# EE445L_Baseline_Schematic.net
KiCad netlist of a schematic drawn in EAGLE
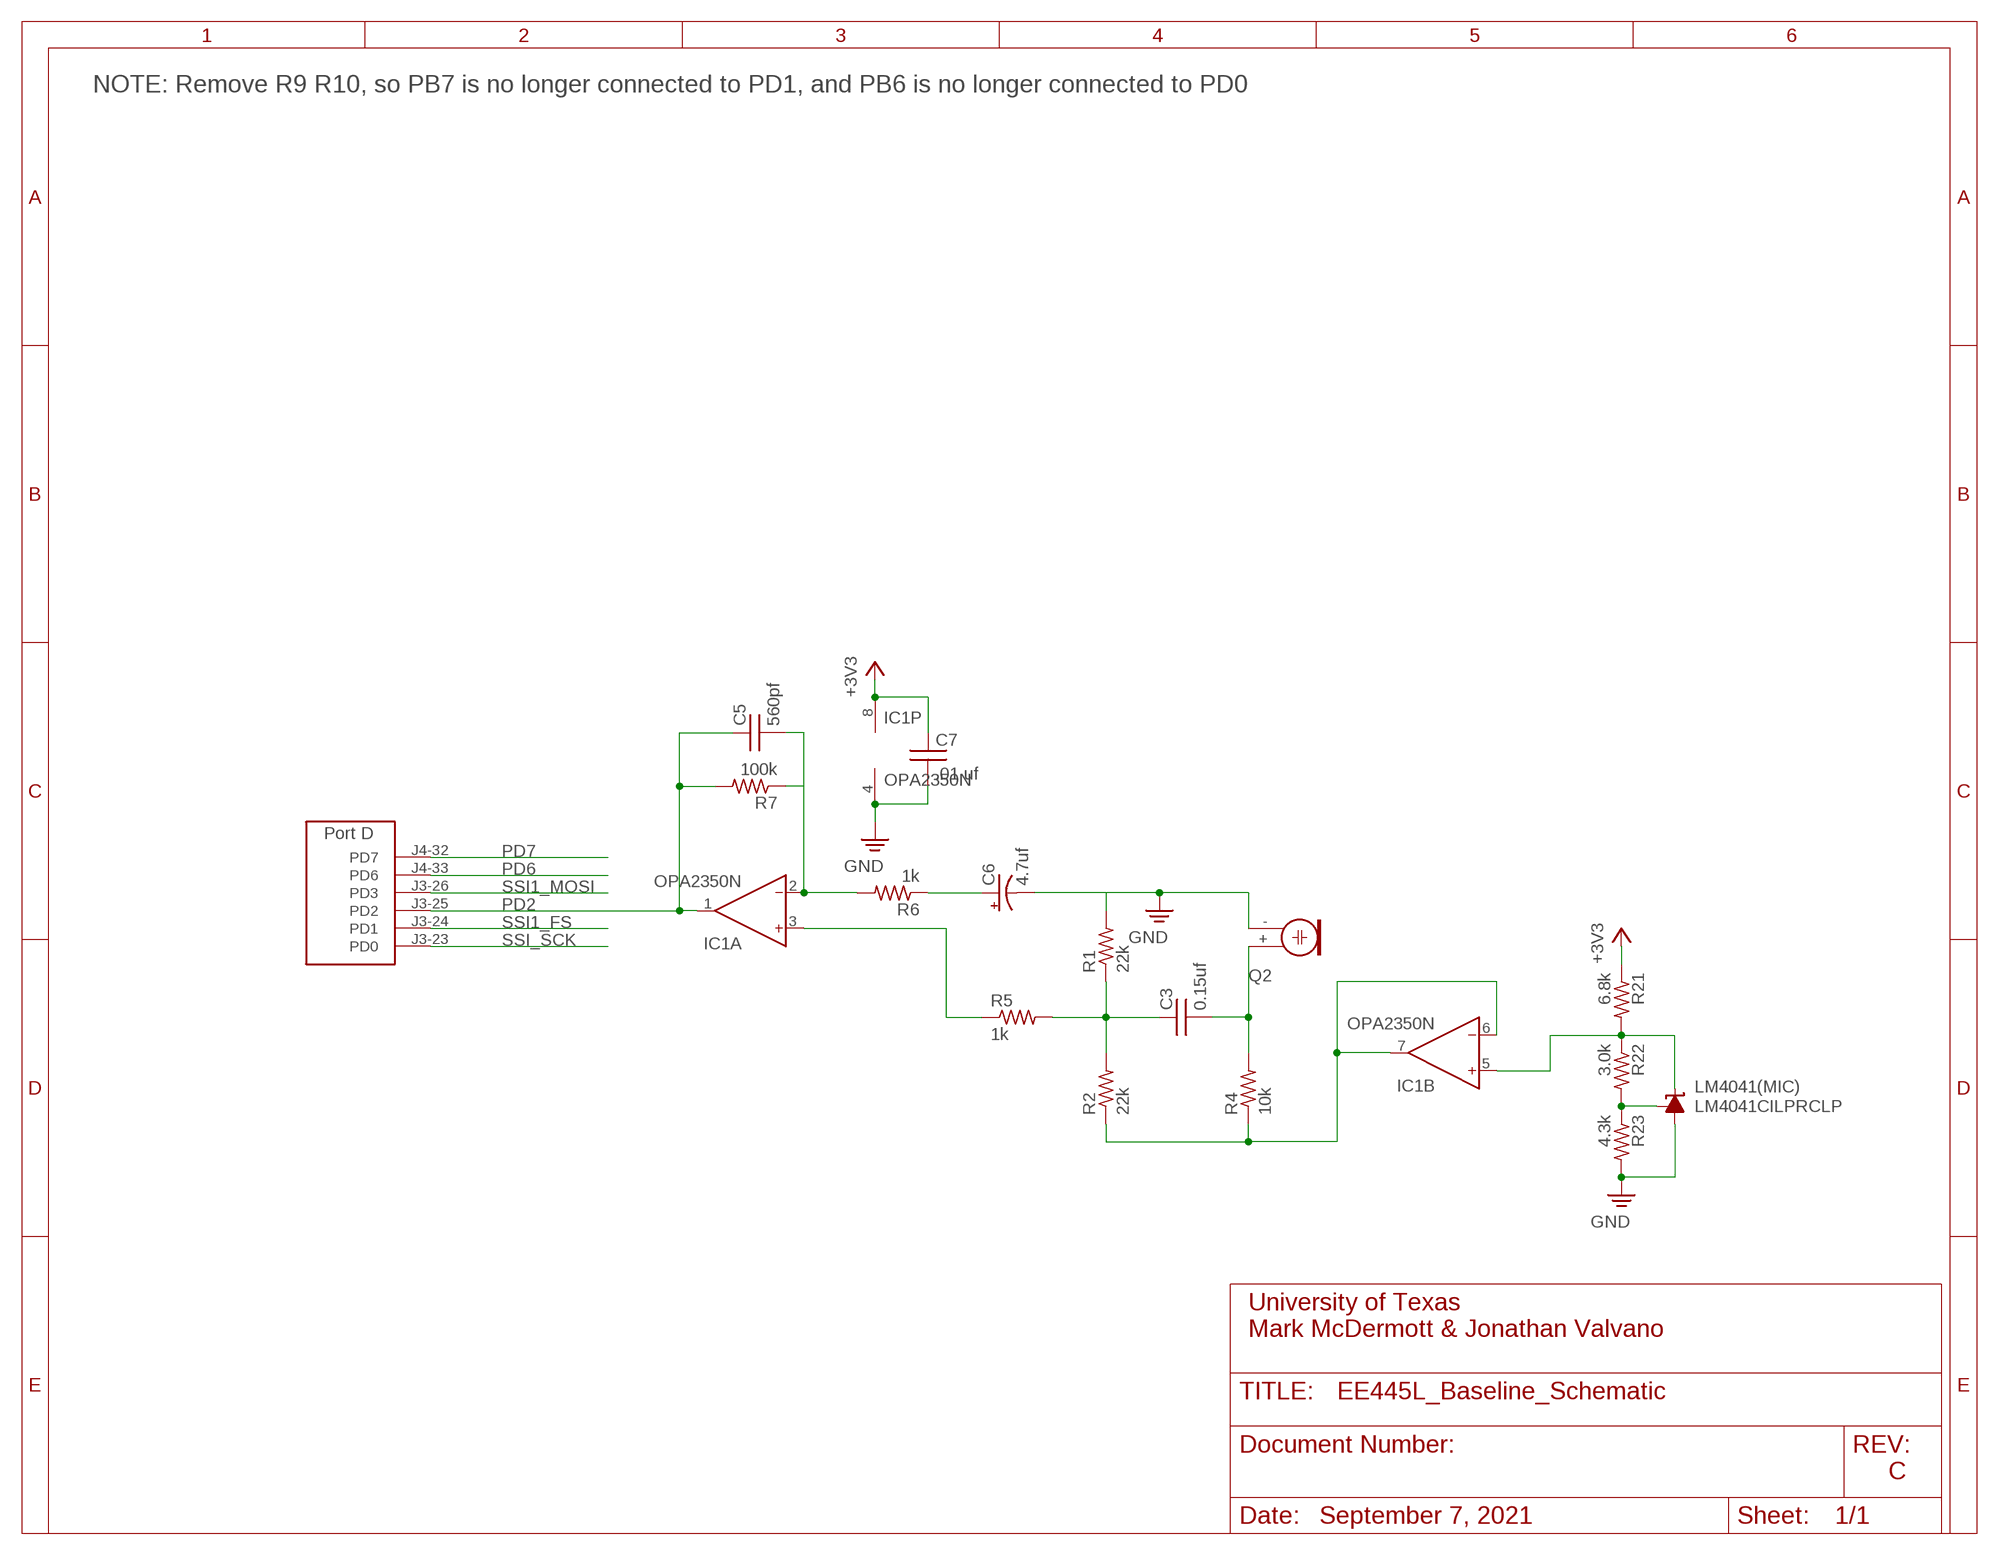
[diagram p0: schematic, sheet 1, part 1 of 2]
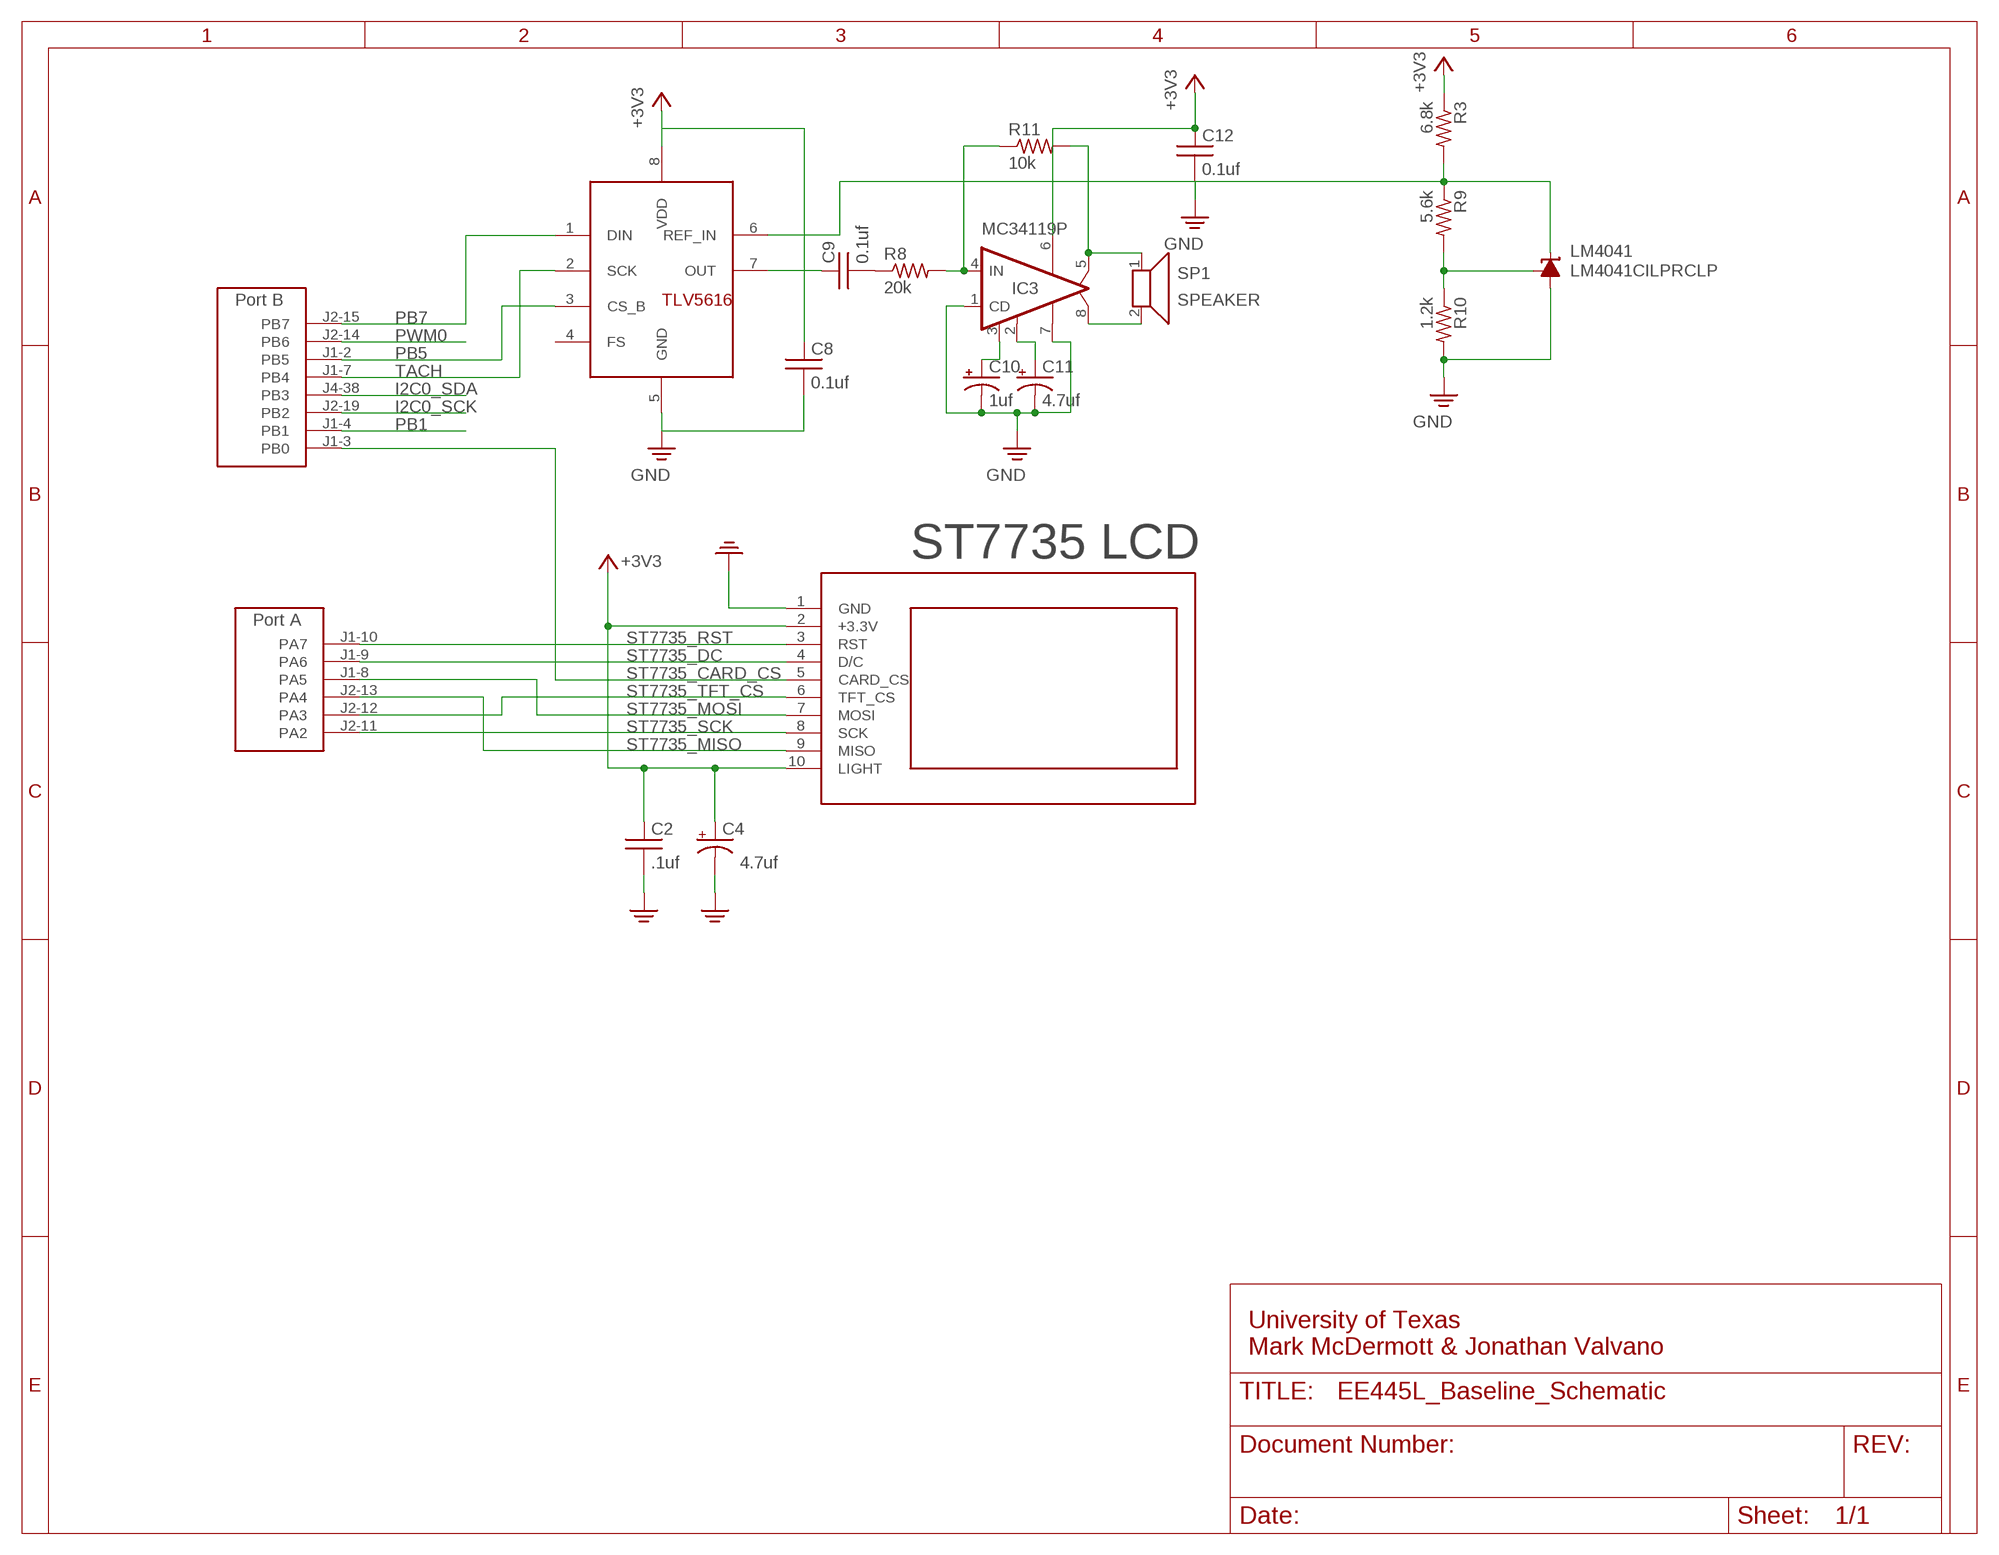
[diagram p1: schematic, sheet 1, part 2 of 2]

(export (version "E")
  (design (tool "Eeschema 10.0.6"))
  (components
    (comp (ref "C2")
      (value ".1uf")
      (footprint "eagle-import:CAP200MIL")
      (libsource (lib "eagle-import") (part "CAPACITOR050-024X044"))
    )
    (comp (ref "C3")
      (value "0.15uf")
      (footprint "eagle-import:CAP100MIL")
      (libsource (lib "eagle-import") (part "CAPACITOR025-024X044"))
    )
    (comp (ref "C4")
      (value "4.7uf")
      (footprint "eagle-import:CAP200MILPOLARIZED")
      (libsource (lib "eagle-import") (part "CAPACITOR_POLARIZEDE5-6"))
    )
    (comp (ref "C5")
      (value "560pf")
      (footprint "eagle-import:CAP100MIL")
      (libsource (lib "eagle-import") (part "CAPACITOR025-024X044"))
    )
    (comp (ref "C6")
      (value "4.7uf")
      (footprint "eagle-import:CAP200MILPOLARIZED")
      (libsource (lib "eagle-import") (part "CAPACITOR_POLARIZEDE5-6"))
    )
    (comp (ref "C7")
      (value ".01 uf")
      (footprint "eagle-import:CAP100MIL")
      (libsource (lib "eagle-import") (part "CAPACITOR025-024X044"))
    )
    (comp (ref "C8")
      (value "0.1uf")
      (footprint "eagle-import:CAP100MIL")
      (libsource (lib "eagle-import") (part "CAPACITOR025-024X044"))
    )
    (comp (ref "C9")
      (value "0.1uf")
      (footprint "eagle-import:CAP100MIL")
      (libsource (lib "eagle-import") (part "CAPACITOR025-024X044"))
    )
    (comp (ref "C10")
      (value "1uf")
      (footprint "eagle-import:CAP200MILPOLARIZED")
      (libsource (lib "eagle-import") (part "CAPACITOR_POLARIZEDE5-6"))
    )
    (comp (ref "C11")
      (value "4.7uf")
      (footprint "eagle-import:CAP200MILPOLARIZED")
      (libsource (lib "eagle-import") (part "CAPACITOR_POLARIZEDE5-6"))
    )
    (comp (ref "C12")
      (value "0.1uf")
      (footprint "eagle-import:CAP100MIL")
      (libsource (lib "eagle-import") (part "CAPACITOR025-024X044"))
    )
    (comp (ref "IC1")
      (value "OPA2350N")
      (footprint "eagle-import:DIL08")
      (libsource (lib "eagle-import") (part "OPA2350N"))
    )
    (comp (ref "IC3")
      (value "MC34119P")
      (footprint "eagle-import:DIL08")
      (libsource (lib "eagle-import") (part "MC34119P"))
    )
    (comp (ref "LM4041")
      (value "LM4041CILPRCLP")
      (footprint "eagle-import:LP_O-PBCY-W3")
      (fields (field (name "MPN") "LM4041CILP"))
      (libsource (lib "eagle-import") (part "LM4041CILPRLPC"))
    )
    (comp (ref "LM4041(MIC)")
      (value "LM4041CILPRCLP")
      (footprint "eagle-import:LP_O-PBCY-W3")
      (fields (field (name "MPN") "LM4041CILP"))
      (libsource (lib "eagle-import") (part "LM4041CILPRLPC"))
    )
    (comp (ref "Q2")
      (value "ELECTRET")
      (footprint "eagle-import:9.7ELECTRET")
      (libsource (lib "eagle-import") (part "ELECTRET"))
    )
    (comp (ref "R1")
      (value "22k")
      (footprint "eagle-import:RES200MIL")
      (libsource (lib "eagle-import") (part "RESISTOR0204/5"))
    )
    (comp (ref "R2")
      (value "22k")
      (footprint "eagle-import:RES200MIL")
      (libsource (lib "eagle-import") (part "RESISTOR0204/5"))
    )
    (comp (ref "R3")
      (value "6.8k")
      (footprint "eagle-import:RES300MIL")
      (libsource (lib "eagle-import") (part "RESISTOR0204/7"))
    )
    (comp (ref "R4")
      (value "10k")
      (footprint "eagle-import:RES200MIL")
      (libsource (lib "eagle-import") (part "RESISTOR0204/5"))
    )
    (comp (ref "R5")
      (value "1k")
      (footprint "eagle-import:RES200MIL")
      (libsource (lib "eagle-import") (part "RESISTOR0204/5"))
    )
    (comp (ref "R6")
      (value "1k")
      (footprint "eagle-import:RES200MIL")
      (libsource (lib "eagle-import") (part "RESISTOR0204/5"))
    )
    (comp (ref "R7")
      (value "100k")
      (footprint "eagle-import:RES200MIL")
      (libsource (lib "eagle-import") (part "RESISTOR0204/5"))
    )
    (comp (ref "R8")
      (value "20k")
      (footprint "eagle-import:RES200MIL")
      (libsource (lib "eagle-import") (part "RESISTOR0204/5"))
    )
    (comp (ref "R9")
      (value "5.6k")
      (footprint "eagle-import:RES300MIL")
      (libsource (lib "eagle-import") (part "RESISTOR0204/7"))
    )
    (comp (ref "R10")
      (value "1.2k")
      (footprint "eagle-import:RES300MIL")
      (libsource (lib "eagle-import") (part "RESISTOR0204/7"))
    )
    (comp (ref "R11")
      (value "10k")
      (footprint "eagle-import:RES300MIL")
      (libsource (lib "eagle-import") (part "RESISTOR0204/7"))
    )
    (comp (ref "R21")
      (value "6.8k")
      (footprint "eagle-import:RES300MIL")
      (libsource (lib "eagle-import") (part "RESISTOR0204/7"))
    )
    (comp (ref "R22")
      (value "3.0k")
      (footprint "eagle-import:RES300MIL")
      (libsource (lib "eagle-import") (part "RESISTOR0204/7"))
    )
    (comp (ref "R23")
      (value "4.3k")
      (footprint "eagle-import:RES300MIL")
      (libsource (lib "eagle-import") (part "RESISTOR0204/7"))
    )
    (comp (ref "SP1")
      (value "SPEAKER")
      (footprint "eagle-import:1X02")
      (libsource (lib "eagle-import") (part "SPEAKER"))
    )
    (comp (ref "U$1")
      (value "TLV5616")
      (footprint "eagle-import:DIL08")
      (libsource (lib "eagle-import") (part "TLV5616"))
    )
    (comp (ref "U$2")
      (value "TM4C_BP")
      (footprint "eagle-import:TM4C_BOOSTER_PACK")
      (libsource (lib "eagle-import") (part "TM4C_BP"))
    )
    (comp (ref "U$3")
      (value "ST7735")
      (footprint "eagle-import:ST7735")
      (libsource (lib "eagle-import") (part "ST7735"))
    )
  )
  (nets
    (net (code "1") (name "+3V3") (class "Default")
      (node (ref "C12") (pin "1") (pinfunction "1_1") (pintype "passive"))
      (node (ref "C2") (pin "1") (pinfunction "1_1") (pintype "passive"))
      (node (ref "C4") (pin "+") (pinfunction "+_+") (pintype "passive"))
      (node (ref "C7") (pin "1") (pinfunction "1_1") (pintype "passive"))
      (node (ref "C8") (pin "1") (pinfunction "1_1") (pintype "passive"))
      (node (ref "IC1") (pin "8") (pinfunction "V+_8") (pintype "power_in"))
      (node (ref "IC3") (pin "6") (pinfunction "VCC_6") (pintype "power_in"))
      (node (ref "R21") (pin "1") (pinfunction "1_1") (pintype "passive"))
      (node (ref "R3") (pin "1") (pinfunction "1_1") (pintype "passive"))
      (node (ref "U$1") (pin "8") (pinfunction "VDD_8") (pintype "bidirectional"))
      (node (ref "U$3") (pin "10") (pinfunction "LIGHT_10") (pintype "bidirectional"))
      (node (ref "U$3") (pin "2") (pinfunction "+3.3V_2") (pintype "bidirectional"))
    )
    (net (code "2") (name "/I2C0_SCK") (class "Default")
      (node (ref "U$2") (pin "J2-19") (pinfunction "PB2_J2-19") (pintype "bidirectional"))
    )
    (net (code "3") (name "/I2C0_SDA") (class "Default")
      (node (ref "U$2") (pin "J4-38") (pinfunction "PB3_J4-38") (pintype "bidirectional"))
    )
    (net (code "4") (name "/PB1") (class "Default")
      (node (ref "U$2") (pin "J1-4") (pinfunction "PB1_J1-4") (pintype "bidirectional"))
    )
    (net (code "5") (name "/PB5") (class "Default")
      (node (ref "U$1") (pin "3") (pinfunction "CS_B_3") (pintype "bidirectional"))
      (node (ref "U$2") (pin "J1-2") (pinfunction "PB5_J1-2") (pintype "bidirectional"))
    )
    (net (code "6") (name "/PB7") (class "Default")
      (node (ref "U$1") (pin "1") (pinfunction "DIN_1") (pintype "bidirectional"))
      (node (ref "U$2") (pin "J2-15") (pinfunction "PB7_J2-15") (pintype "bidirectional"))
    )
    (net (code "7") (name "/PD2") (class "Default")
      (node (ref "C5") (pin "1") (pinfunction "1_1") (pintype "passive"))
      (node (ref "IC1") (pin "1") (pinfunction "OUT_1") (pintype "output"))
      (node (ref "R7") (pin "2") (pinfunction "2_2") (pintype "passive"))
      (node (ref "U$2") (pin "J3-25") (pinfunction "PD2_J3-25") (pintype "bidirectional"))
    )
    (net (code "8") (name "/PD6") (class "Default")
      (node (ref "U$2") (pin "J4-33") (pinfunction "PD6_J4-33") (pintype "bidirectional"))
    )
    (net (code "9") (name "/PD7") (class "Default")
      (node (ref "U$2") (pin "J4-32") (pinfunction "PD7_J4-32") (pintype "bidirectional"))
    )
    (net (code "10") (name "/PWM0") (class "Default")
      (node (ref "U$2") (pin "J2-14") (pinfunction "PB6_J2-14") (pintype "bidirectional"))
    )
    (net (code "11") (name "/SSI1_FS") (class "Default")
      (node (ref "U$2") (pin "J3-24") (pinfunction "PD1_J3-24") (pintype "bidirectional"))
    )
    (net (code "12") (name "/SSI1_MOSI") (class "Default")
      (node (ref "U$2") (pin "J3-26") (pinfunction "PD3_J3-26") (pintype "bidirectional"))
    )
    (net (code "13") (name "/SSI_SCK") (class "Default")
      (node (ref "U$2") (pin "J3-23") (pinfunction "PD0_J3-23") (pintype "bidirectional"))
    )
    (net (code "14") (name "/ST7735_CARD_CS") (class "Default")
      (node (ref "U$2") (pin "J1-3") (pinfunction "PB0_J1-3") (pintype "bidirectional"))
      (node (ref "U$3") (pin "5") (pinfunction "CARD_CS_5") (pintype "bidirectional"))
    )
    (net (code "15") (name "/ST7735_DC") (class "Default")
      (node (ref "U$2") (pin "J1-9") (pinfunction "PA6_J1-9") (pintype "bidirectional"))
      (node (ref "U$3") (pin "4") (pinfunction "D/C_4") (pintype "bidirectional"))
    )
    (net (code "16") (name "/ST7735_MISO") (class "Default")
      (node (ref "U$2") (pin "J2-13") (pinfunction "PA4_J2-13") (pintype "bidirectional"))
      (node (ref "U$3") (pin "9") (pinfunction "MISO_9") (pintype "bidirectional"))
    )
    (net (code "17") (name "/ST7735_MOSI") (class "Default")
      (node (ref "U$2") (pin "J1-8") (pinfunction "PA5_J1-8") (pintype "bidirectional"))
      (node (ref "U$3") (pin "7") (pinfunction "MOSI_7") (pintype "bidirectional"))
    )
    (net (code "18") (name "/ST7735_RST") (class "Default")
      (node (ref "U$2") (pin "J1-10") (pinfunction "PA7_J1-10") (pintype "bidirectional"))
      (node (ref "U$3") (pin "3") (pinfunction "RST_3") (pintype "bidirectional"))
    )
    (net (code "19") (name "/ST7735_SCK") (class "Default")
      (node (ref "U$2") (pin "J2-11") (pinfunction "PA2_J2-11") (pintype "bidirectional"))
      (node (ref "U$3") (pin "8") (pinfunction "SCK_8") (pintype "bidirectional"))
    )
    (net (code "20") (name "/ST7735_TFT_CS") (class "Default")
      (node (ref "U$2") (pin "J2-12") (pinfunction "PA3_J2-12") (pintype "bidirectional"))
      (node (ref "U$3") (pin "6") (pinfunction "TFT_CS_6") (pintype "bidirectional"))
    )
    (net (code "21") (name "/TACH") (class "Default")
      (node (ref "U$1") (pin "2") (pinfunction "SCK_2") (pintype "bidirectional"))
      (node (ref "U$2") (pin "J1-7") (pinfunction "PB4_J1-7") (pintype "bidirectional"))
    )
    (net (code "22") (name "GND") (class "Default")
      (node (ref "C10") (pin "-") (pinfunction "-_-") (pintype "passive"))
      (node (ref "C11") (pin "-") (pinfunction "-_-") (pintype "passive"))
      (node (ref "C12") (pin "2") (pinfunction "2_2") (pintype "passive"))
      (node (ref "C2") (pin "2") (pinfunction "2_2") (pintype "passive"))
      (node (ref "C4") (pin "-") (pinfunction "-_-") (pintype "passive"))
      (node (ref "C6") (pin "-") (pinfunction "-_-") (pintype "passive"))
      (node (ref "C7") (pin "2") (pinfunction "2_2") (pintype "passive"))
      (node (ref "C8") (pin "2") (pinfunction "2_2") (pintype "passive"))
      (node (ref "IC1") (pin "4") (pinfunction "V-_4") (pintype "power_in"))
      (node (ref "IC3") (pin "1") (pinfunction "CD_1") (pintype "passive"))
      (node (ref "IC3") (pin "7") (pinfunction "GND_7") (pintype "power_in"))
      (node (ref "LM4041") (pin "3") (pinfunction "A_3") (pintype "passive"))
      (node (ref "LM4041(MIC)") (pin "3") (pinfunction "A_3") (pintype "passive"))
      (node (ref "Q2") (pin "-") (pinfunction "1_-") (pintype "passive"))
      (node (ref "R1") (pin "2") (pinfunction "2_2") (pintype "passive"))
      (node (ref "R10") (pin "2") (pinfunction "2_2") (pintype "passive"))
      (node (ref "R23") (pin "2") (pinfunction "2_2") (pintype "passive"))
      (node (ref "U$1") (pin "5") (pinfunction "GND_5") (pintype "bidirectional"))
      (node (ref "U$3") (pin "1") (pinfunction "GND_1") (pintype "bidirectional"))
    )
    (net (code "23") (name "Net-(C3-Pad1)") (class "Default")
      (node (ref "C3") (pin "1") (pinfunction "1_1") (pintype "passive"))
      (node (ref "R1") (pin "1") (pinfunction "1_1") (pintype "passive"))
      (node (ref "R2") (pin "2") (pinfunction "2_2") (pintype "passive"))
      (node (ref "R5") (pin "2") (pinfunction "2_2") (pintype "passive"))
    )
    (net (code "24") (name "Net-(C6-Pad+)") (class "Default")
      (node (ref "C6") (pin "+") (pinfunction "+_+") (pintype "passive"))
      (node (ref "R6") (pin "1") (pinfunction "1_1") (pintype "passive"))
    )
    (net (code "25") (name "Net-(C9-Pad2)") (class "Default")
      (node (ref "C9") (pin "2") (pinfunction "2_2") (pintype "passive"))
      (node (ref "R8") (pin "1") (pinfunction "1_1") (pintype "passive"))
    )
    (net (code "26") (name "Net-(IC1A-IN+)") (class "Default")
      (node (ref "IC1") (pin "3") (pinfunction "IN+_3") (pintype "input"))
      (node (ref "R5") (pin "1") (pinfunction "1_1") (pintype "passive"))
    )
    (net (code "27") (name "Net-(IC1A-IN-)") (class "Default")
      (node (ref "C5") (pin "2") (pinfunction "2_2") (pintype "passive"))
      (node (ref "IC1") (pin "2") (pinfunction "IN-_2") (pintype "input"))
      (node (ref "R6") (pin "2") (pinfunction "2_2") (pintype "passive"))
      (node (ref "R7") (pin "1") (pinfunction "1_1") (pintype "passive"))
    )
    (net (code "28") (name "Net-(IC1B-IN+)") (class "Default")
      (node (ref "IC1") (pin "5") (pinfunction "IN+_5") (pintype "input"))
      (node (ref "LM4041(MIC)") (pin "2") (pinfunction "C_2") (pintype "passive"))
      (node (ref "R21") (pin "2") (pinfunction "2_2") (pintype "passive"))
      (node (ref "R22") (pin "1") (pinfunction "1_1") (pintype "passive"))
    )
    (net (code "29") (name "Net-(IC1B-IN-)") (class "Default")
      (node (ref "IC1") (pin "6") (pinfunction "IN-_6") (pintype "input"))
      (node (ref "IC1") (pin "7") (pinfunction "OUT_7") (pintype "output"))
      (node (ref "R2") (pin "1") (pinfunction "1_1") (pintype "passive"))
      (node (ref "R4") (pin "1") (pinfunction "1_1") (pintype "passive"))
    )
    (net (code "30") (name "Net-(IC3-FC1)") (class "Default")
      (node (ref "C10") (pin "+") (pinfunction "+_+") (pintype "passive"))
      (node (ref "IC3") (pin "3") (pinfunction "FC1_3") (pintype "passive"))
    )
    (net (code "31") (name "Net-(IC3-FC2)") (class "Default")
      (node (ref "C11") (pin "+") (pinfunction "+_+") (pintype "passive"))
      (node (ref "IC3") (pin "2") (pinfunction "FC2_2") (pintype "passive"))
    )
    (net (code "32") (name "Net-(IC3-IN)") (class "Default")
      (node (ref "IC3") (pin "4") (pinfunction "IN_4") (pintype "input"))
      (node (ref "R11") (pin "1") (pinfunction "1_1") (pintype "passive"))
      (node (ref "R8") (pin "2") (pinfunction "2_2") (pintype "passive"))
    )
    (net (code "33") (name "Net-(IC3-VO1)") (class "Default")
      (node (ref "IC3") (pin "5") (pinfunction "VO1_5") (pintype "output"))
      (node (ref "R11") (pin "2") (pinfunction "2_2") (pintype "passive"))
      (node (ref "SP1") (pin "1") (pinfunction "1_1") (pintype "passive"))
    )
    (net (code "34") (name "Net-(IC3-VO2)") (class "Default")
      (node (ref "IC3") (pin "8") (pinfunction "VO2_8") (pintype "output"))
      (node (ref "SP1") (pin "2") (pinfunction "2_2") (pintype "passive"))
    )
    (net (code "35") (name "Net-(LM4041(MIC)-FB)") (class "Default")
      (node (ref "LM4041(MIC)") (pin "1") (pinfunction "FB_1") (pintype "passive"))
      (node (ref "R22") (pin "2") (pinfunction "2_2") (pintype "passive"))
      (node (ref "R23") (pin "1") (pinfunction "1_1") (pintype "passive"))
    )
    (net (code "36") (name "Net-(LM4041-C)") (class "Default")
      (node (ref "LM4041") (pin "2") (pinfunction "C_2") (pintype "passive"))
      (node (ref "R3") (pin "2") (pinfunction "2_2") (pintype "passive"))
      (node (ref "R9") (pin "1") (pinfunction "1_1") (pintype "passive"))
      (node (ref "U$1") (pin "6") (pinfunction "REF_IN_6") (pintype "bidirectional"))
    )
    (net (code "37") (name "Net-(LM4041-FB)") (class "Default")
      (node (ref "LM4041") (pin "1") (pinfunction "FB_1") (pintype "passive"))
      (node (ref "R10") (pin "1") (pinfunction "1_1") (pintype "passive"))
      (node (ref "R9") (pin "2") (pinfunction "2_2") (pintype "passive"))
    )
    (net (code "38") (name "Net-(Q2-2)") (class "Default")
      (node (ref "C3") (pin "2") (pinfunction "2_2") (pintype "passive"))
      (node (ref "Q2") (pin "+") (pinfunction "2_+") (pintype "passive"))
      (node (ref "R4") (pin "2") (pinfunction "2_2") (pintype "passive"))
    )
    (net (code "39") (name "Net-(U$1-OUT)") (class "Default")
      (node (ref "C9") (pin "1") (pinfunction "1_1") (pintype "passive"))
      (node (ref "U$1") (pin "7") (pinfunction "OUT_7") (pintype "bidirectional"))
    )
    (net (code "40") (name "unconnected-(U$1-FS-Pad4)") (class "Default")
      (node (ref "U$1") (pin "4") (pinfunction "FS_4") (pintype "bidirectional"))
    )
  )
)
